# SPI_Flash.net
KiCad netlist of a schematic drawn in Altium Designer
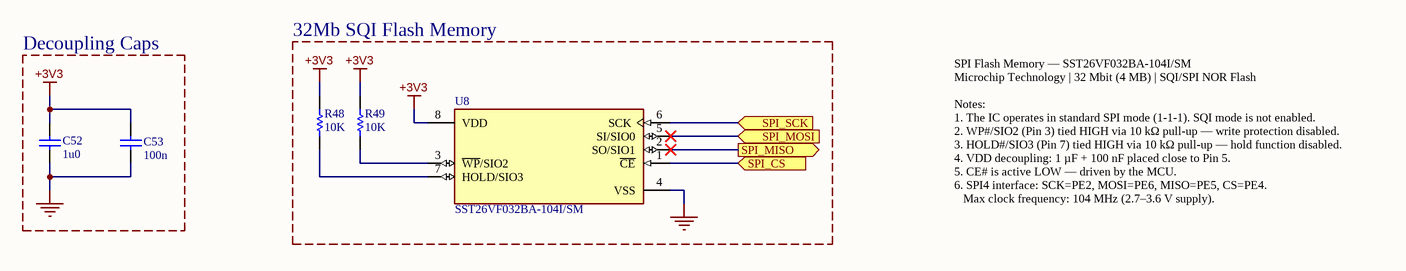
[diagram p0: SPI_Flash.SchDoc]

(export (version "E")
  (design (tool "Eeschema 10.0.6"))
  (components
    (comp (ref "C52")
      (value "1u0")
      (footprint "0603C")
      (description "Capacitor")
      (fields (field (name "TOLERANCE") "10%"))
      (libsource (lib "MB963_1") (part "CAP SMD 0603  X5R 1µF 25V 10%"))
    )
    (comp (ref "C53")
      (value "100n")
      (footprint "0603C")
      (description "Capacitor")
      (fields (field (name "PUBLISHER") "Altium Limited"))
      (libsource (lib "Miscellaneous Devices") (part "Cap"))
    )
    (comp (ref "R48")
      (value "10K")
      (footprint "0603R")
      (description "Resistor")
      (fields (field (name "PUBLISHER") "Altium Limited"))
      (libsource (lib "Miscellaneous Devices") (part "res1"))
    )
    (comp (ref "R49")
      (value "10K")
      (footprint "0603R")
      (description "Resistor")
      (fields (field (name "PUBLISHER") "Altium Limited"))
      (libsource (lib "Miscellaneous Devices") (part "res1"))
    )
    (comp (ref "U8")
      (value "SST26VF032BA-104I/SM")
      (footprint "FP-C04-056-IPC_A")
      (description "IC FLASH 32MBIT SPI/QUAD 8SOIJ")
      (libsource (lib "Altium Content Vault") (part "8c876756a47509e317040860eb18f62"))
    )
  )
  (nets
    (net (code "1") (name "+3V3") (class "Default")
      (node (ref "C52") (pin "1") (pinfunction "1_1") (pintype "passive"))
      (node (ref "C53") (pin "1") (pinfunction "1_1") (pintype "passive"))
      (node (ref "R48") (pin "1") (pinfunction "1_1") (pintype "passive"))
      (node (ref "R49") (pin "1") (pinfunction "1_1") (pintype "passive"))
      (node (ref "U8") (pin "8") (pinfunction "VDD_8") (pintype "power_in"))
    )
    (net (code "2") (name "/SPI_CS") (class "Default")
      (node (ref "U8") (pin "1") (pinfunction "~{CE}_1") (pintype "input"))
    )
    (net (code "3") (name "/SPI_MISO") (class "Default")
      (node (ref "U8") (pin "2") (pinfunction "SO/SIO1_2") (pintype "bidirectional+no_connect"))
    )
    (net (code "4") (name "/SPI_MOSI") (class "Default")
      (node (ref "U8") (pin "5") (pinfunction "SI/SIO0_5") (pintype "bidirectional+no_connect"))
    )
    (net (code "5") (name "/SPI_SCK") (class "Default")
      (node (ref "U8") (pin "6") (pinfunction "SCK_6") (pintype "input"))
    )
    (net (code "6") (name "GND") (class "Default")
      (node (ref "C52") (pin "2") (pinfunction "2_2") (pintype "passive"))
      (node (ref "C53") (pin "2") (pinfunction "2_2") (pintype "passive"))
      (node (ref "U8") (pin "4") (pinfunction "VSS_4") (pintype "power_in"))
    )
    (net (code "7") (name "Net-(U8-HOLD{slash}SIO3)") (class "Default")
      (node (ref "R48") (pin "2") (pinfunction "2_2") (pintype "passive"))
      (node (ref "U8") (pin "7") (pinfunction "HOLD/SIO3_7") (pintype "bidirectional"))
    )
    (net (code "8") (name "Net-(U8-~{WP}{slash}SIO2)") (class "Default")
      (node (ref "R49") (pin "2") (pinfunction "2_2") (pintype "passive"))
      (node (ref "U8") (pin "3") (pinfunction "~{WP}/SIO2_3") (pintype "bidirectional"))
    )
  )
)
